# REGENIX_Convertisseurs.net
KiCad netlist of a schematic drawn in Altium Designer
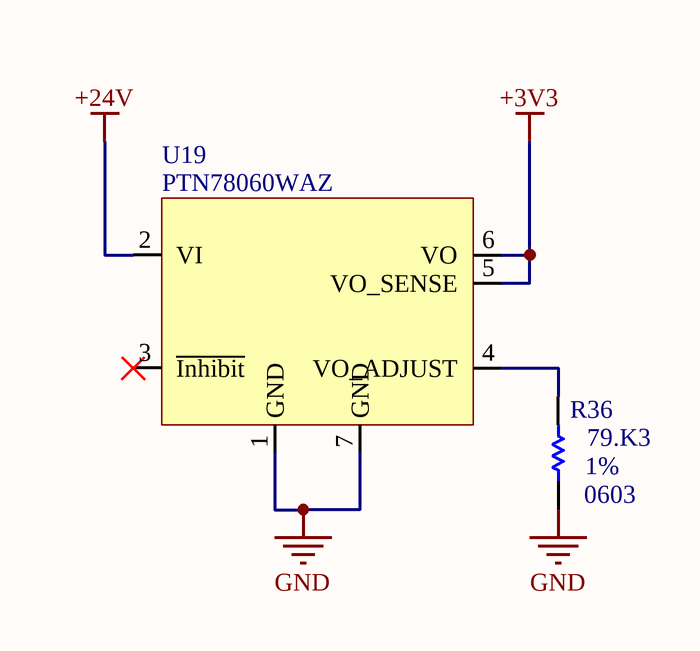
[diagram p0: REGENIX_Convertisseurs.SchDoc]

(export (version "E")
  (design (tool "Eeschema 10.0.6"))
  (components
    (comp (ref "R36")
      (value "79.K3")
      (footprint "RES_0603")
      (description "RES - 0603")
      (fields
        (field (name "PACKAGE") "0603")
        (field (name "PRECISION") "1%")
        (field (name "CREATEDBY") "Jonathan Bouchard")
      )
      (libsource (lib "S7CAS_LIB2023") (part "RES - 0603"))
    )
    (comp (ref "U19")
      (value "PTN78060WAZ")
      (footprint "REG_SWR_PTN78060WAZ")
      (description "REG - DC-DC Module 2.5V~12.6V ADJ OUT 3A  - 7-SMD")
      (fields
        (field (name "TOLERANCE") "3%")
        (field (name "CREATEDBY/DATE") "Danae D-F 28 juin 2019")
        (field (name "VERIFIEDBY") "Nicolas V. (2019-07-15)")
      )
      (libsource (lib "S7CAS_LIB2023") (part "REG_SWR_PTN78060WAZ"))
    )
  )
  (nets
    (net (code "1") (name "+3V3") (class "Default")
      (node (ref "U19") (pin "5") (pinfunction "VO_SENSE_5") (pintype "passive"))
      (node (ref "U19") (pin "6") (pinfunction "VO_6") (pintype "passive"))
    )
    (net (code "2") (name "+24V") (class "Default")
      (node (ref "U19") (pin "2") (pinfunction "VI_2") (pintype "passive"))
    )
    (net (code "3") (name "GND") (class "Default")
      (node (ref "R36") (pin "1") (pinfunction "1_1") (pintype "passive"))
      (node (ref "U19") (pin "1") (pinfunction "GND_1") (pintype "passive"))
      (node (ref "U19") (pin "7") (pinfunction "GND_7") (pintype "passive"))
    )
    (net (code "4") (name "Net-(U19-VO_ADJUST)") (class "Default")
      (node (ref "R36") (pin "2") (pinfunction "2_2") (pintype "passive"))
      (node (ref "U19") (pin "4") (pinfunction "VO_ADJUST_4") (pintype "passive"))
    )
    (net (code "5") (name "unconnected-(U19-Inhibit-Pad3)") (class "Default")
      (node (ref "U19") (pin "3") (pinfunction "Inhibit_3") (pintype "passive+no_connect"))
    )
  )
)
